# AmigaUSBMouse.net
KiCad netlist of a schematic drawn in EAGLE
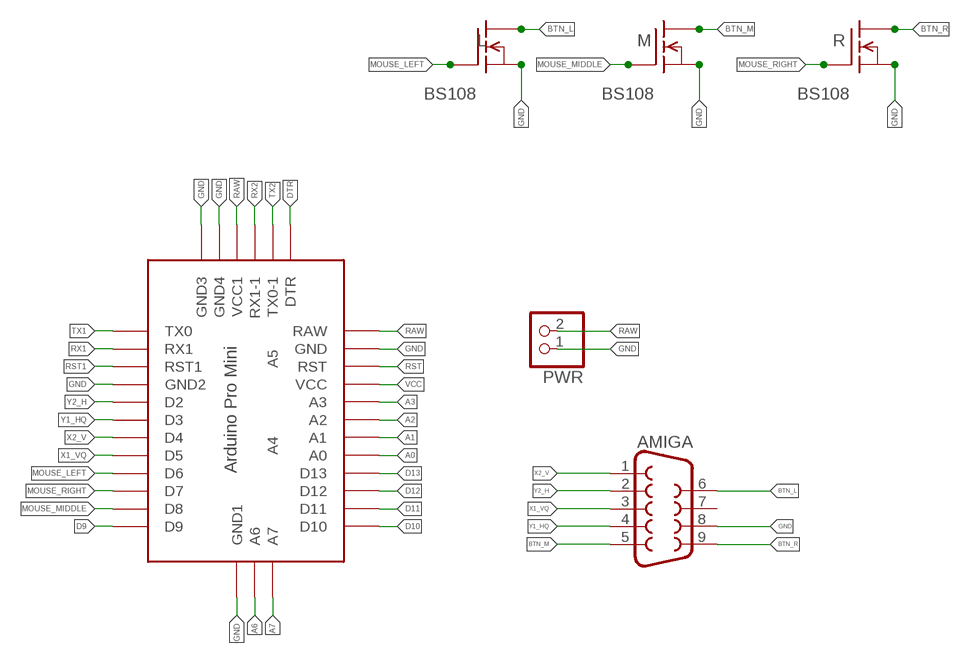
[diagram p0: schematic, sheet 1]

(export (version "E")
  (design (tool "Eeschema 10.0.6"))
  (components
    (comp (ref "AMIGA")
      (value "DB9FEMALE")
      (footprint "eagle-import:DB9")
      (libsource (lib "eagle-import") (part "DB9FEMALE"))
    )
    (comp (ref "L")
      (value "BS108")
      (footprint "eagle-import:TO92-INLINE")
      (libsource (lib "eagle-import") (part "FQN1N50CI"))
    )
    (comp (ref "M")
      (value "BS108")
      (footprint "eagle-import:TO92-INLINE")
      (libsource (lib "eagle-import") (part "FQN1N50CI"))
    )
    (comp (ref "PWR")
      (value "PINHD-1X2")
      (footprint "eagle-import:1X02")
      (libsource (lib "eagle-import") (part "PINHD-1X2"))
    )
    (comp (ref "R")
      (value "BS108")
      (footprint "eagle-import:TO92-INLINE")
      (libsource (lib "eagle-import") (part "FQN1N50CI"))
    )
    (comp (ref "U$1")
      (value "ABK-PRO-MINI")
      (footprint "eagle-import:ABK-PRO-MINI")
      (libsource (lib "eagle-import") (part "ABK-PRO-MINI"))
    )
  )
  (nets
    (net (code "1") (name "A0") (class "Default")
      (node (ref "U$1") (pin "A0") (pinfunction "A0_A0") (pintype "bidirectional"))
    )
    (net (code "2") (name "A1") (class "Default")
      (node (ref "U$1") (pin "A1") (pinfunction "A1_A1") (pintype "bidirectional"))
    )
    (net (code "3") (name "A2") (class "Default")
      (node (ref "U$1") (pin "A2") (pinfunction "A2_A2") (pintype "bidirectional"))
    )
    (net (code "4") (name "A3") (class "Default")
      (node (ref "U$1") (pin "A3") (pinfunction "A3_A3") (pintype "bidirectional"))
    )
    (net (code "5") (name "A6") (class "Default")
      (node (ref "U$1") (pin "A6") (pinfunction "A6_A6") (pintype "bidirectional"))
    )
    (net (code "6") (name "A7") (class "Default")
      (node (ref "U$1") (pin "A7") (pinfunction "A7_A7") (pintype "bidirectional"))
    )
    (net (code "7") (name "BTN_L") (class "Default")
      (node (ref "AMIGA") (pin "6") (pinfunction "6_6") (pintype "passive"))
      (node (ref "L") (pin "1") (pinfunction "D_1") (pintype "passive"))
    )
    (net (code "8") (name "BTN_M") (class "Default")
      (node (ref "AMIGA") (pin "5") (pinfunction "5_5") (pintype "passive"))
      (node (ref "M") (pin "1") (pinfunction "D_1") (pintype "passive"))
    )
    (net (code "9") (name "BTN_R") (class "Default")
      (node (ref "AMIGA") (pin "9") (pinfunction "9_9") (pintype "passive"))
      (node (ref "R") (pin "1") (pinfunction "D_1") (pintype "passive"))
    )
    (net (code "10") (name "D9") (class "Default")
      (node (ref "U$1") (pin "D9") (pinfunction "D9_D9") (pintype "bidirectional"))
    )
    (net (code "11") (name "D10") (class "Default")
      (node (ref "U$1") (pin "D10") (pinfunction "D10_D10") (pintype "bidirectional"))
    )
    (net (code "12") (name "D11") (class "Default")
      (node (ref "U$1") (pin "D11") (pinfunction "D11_D11") (pintype "bidirectional"))
    )
    (net (code "13") (name "D12") (class "Default")
      (node (ref "U$1") (pin "D12") (pinfunction "D12_D12") (pintype "bidirectional"))
    )
    (net (code "14") (name "D13") (class "Default")
      (node (ref "U$1") (pin "D13") (pinfunction "D13_D13") (pintype "bidirectional"))
    )
    (net (code "15") (name "DTR") (class "Default")
      (node (ref "U$1") (pin "DTR") (pinfunction "DTR_DTR") (pintype "bidirectional"))
    )
    (net (code "16") (name "GND") (class "Default")
      (node (ref "AMIGA") (pin "8") (pinfunction "8_8") (pintype "passive"))
      (node (ref "L") (pin "3") (pinfunction "S_3") (pintype "passive"))
      (node (ref "M") (pin "3") (pinfunction "S_3") (pintype "passive"))
      (node (ref "PWR") (pin "1") (pinfunction "1_1") (pintype "passive"))
      (node (ref "R") (pin "3") (pinfunction "S_3") (pintype "passive"))
      (node (ref "U$1") (pin "GND") (pinfunction "GND_GND") (pintype "bidirectional"))
      (node (ref "U$1") (pin "GND1") (pinfunction "GND2_GND1") (pintype "bidirectional"))
      (node (ref "U$1") (pin "GND2") (pinfunction "GND3_GND2") (pintype "bidirectional"))
      (node (ref "U$1") (pin "GND3") (pinfunction "GND4_GND3") (pintype "bidirectional"))
      (node (ref "U$1") (pin "GND4") (pinfunction "GND1_GND4") (pintype "bidirectional"))
    )
    (net (code "17") (name "MOUSE_LEFT") (class "Default")
      (node (ref "L") (pin "2") (pinfunction "G_2") (pintype "passive"))
      (node (ref "U$1") (pin "D6") (pinfunction "D6_D6") (pintype "bidirectional"))
    )
    (net (code "18") (name "MOUSE_MIDDLE") (class "Default")
      (node (ref "M") (pin "2") (pinfunction "G_2") (pintype "passive"))
      (node (ref "U$1") (pin "D8") (pinfunction "D8_D8") (pintype "bidirectional"))
    )
    (net (code "19") (name "MOUSE_RIGHT") (class "Default")
      (node (ref "R") (pin "2") (pinfunction "G_2") (pintype "passive"))
      (node (ref "U$1") (pin "D7") (pinfunction "D7_D7") (pintype "bidirectional"))
    )
    (net (code "20") (name "RAW") (class "Default")
      (node (ref "PWR") (pin "2") (pinfunction "2_2") (pintype "passive"))
      (node (ref "U$1") (pin "RAW") (pinfunction "RAW_RAW") (pintype "bidirectional"))
      (node (ref "U$1") (pin "VCC1") (pinfunction "VCC1_VCC1") (pintype "bidirectional"))
    )
    (net (code "21") (name "RST") (class "Default")
      (node (ref "U$1") (pin "RST") (pinfunction "RST_RST") (pintype "bidirectional"))
    )
    (net (code "22") (name "RST1") (class "Default")
      (node (ref "U$1") (pin "RST1") (pinfunction "RST1_RST1") (pintype "bidirectional"))
    )
    (net (code "23") (name "RX1") (class "Default")
      (node (ref "U$1") (pin "RX1") (pinfunction "RX1_RX1") (pintype "bidirectional"))
    )
    (net (code "24") (name "RX2") (class "Default")
      (node (ref "U$1") (pin "RX1-1") (pinfunction "RX1-1_RX1-1") (pintype "bidirectional"))
    )
    (net (code "25") (name "TX1") (class "Default")
      (node (ref "U$1") (pin "TX0") (pinfunction "TX0_TX0") (pintype "bidirectional"))
    )
    (net (code "26") (name "TX2") (class "Default")
      (node (ref "U$1") (pin "TX0-1") (pinfunction "TX0-1_TX0-1") (pintype "bidirectional"))
    )
    (net (code "27") (name "VCC") (class "Default")
      (node (ref "U$1") (pin "VCC") (pinfunction "VCC_VCC") (pintype "bidirectional"))
    )
    (net (code "28") (name "X1_VQ") (class "Default")
      (node (ref "AMIGA") (pin "3") (pinfunction "3_3") (pintype "passive"))
      (node (ref "U$1") (pin "D5") (pinfunction "D5_D5") (pintype "bidirectional"))
    )
    (net (code "29") (name "X2_V") (class "Default")
      (node (ref "AMIGA") (pin "1") (pinfunction "1_1") (pintype "passive"))
      (node (ref "U$1") (pin "D4") (pinfunction "D4_D4") (pintype "bidirectional"))
    )
    (net (code "30") (name "Y1_HQ") (class "Default")
      (node (ref "AMIGA") (pin "4") (pinfunction "4_4") (pintype "passive"))
      (node (ref "U$1") (pin "D3") (pinfunction "D3_D3") (pintype "bidirectional"))
    )
    (net (code "31") (name "Y2_H") (class "Default")
      (node (ref "AMIGA") (pin "2") (pinfunction "2_2") (pintype "passive"))
      (node (ref "U$1") (pin "D2") (pinfunction "D2_D2") (pintype "bidirectional"))
    )
    (net (code "32") (name "unconnected-(AMIGA-Pad7)") (class "Default")
      (node (ref "AMIGA") (pin "7") (pinfunction "7_7") (pintype "passive"))
    )
    (net (code "33") (name "unconnected-(U$1-PadA4)") (class "Default")
      (node (ref "U$1") (pin "A4") (pinfunction "A4_A4") (pintype "bidirectional"))
    )
    (net (code "34") (name "unconnected-(U$1-PadA5)") (class "Default")
      (node (ref "U$1") (pin "A5") (pinfunction "A5_A5") (pintype "bidirectional"))
    )
  )
)
